# 05_iMX_8X_PCIE.net
KiCad netlist of a schematic drawn in Altium Designer
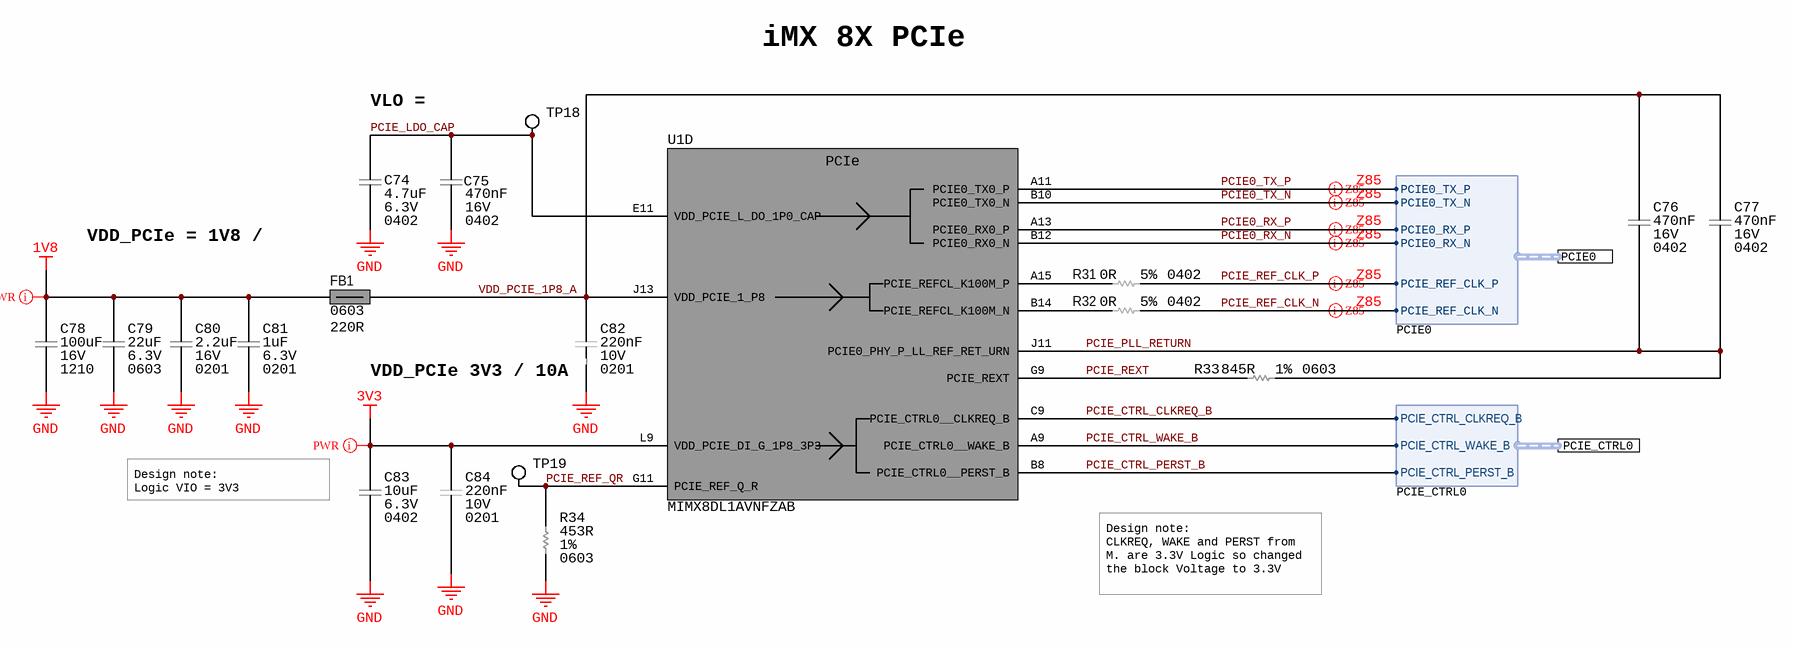
[diagram p0: 05_iMX 8X_PCIE.SchDoc]

(export (version "E")
  (design (tool "Eeschema 10.0.6"))
  (components
    (comp (ref "C74")
      (value "C1005X5R0J475M050BC")
      (footprint "CAP_0402_CAPC1005X05N")
      (description "Multilayer Ceramic Capacitor, 4.7 uF, 6.3 V, ± 20%, X5R, 0402 [1005 Metric]")
      (fields
        (field (name "MANUFACTURER") "TDK")
        (field (name "TOLERANCE") "20%")
        (field (name "CAPACITANCE") "4.7uF")
        (field (name "VOLTAGE RATING") "6.3V")
        (field (name "CASE/PACKAGE") "0402")
      )
      (libsource (lib "Electronic Devices_LIB") (part "CAP_4.7UF_6.3V_X5R_0402"))
    )
    (comp (ref "C75")
      (value "GRT155R61C474KE01D")
      (footprint "CAP_0402_CAPC1005X05N")
      (description "0402 0.47 uF 16 V ±10 % Tolerance X5R SMT Multilayer Ceramic Capacitor")
      (fields
        (field (name "MANUFACTURER") "Murata")
        (field (name "TOLERANCE") "10%")
        (field (name "VOLTAGE RATING") "16V")
        (field (name "CAPACITANCE") "470nF")
        (field (name "CASE/PACKAGE") "0402")
      )
      (libsource (lib "Electronic Devices_LIB") (part "CAP_0.47UF_16V_X5R_0402"))
    )
    (comp (ref "C76")
      (value "GRT155R61C474KE01D")
      (footprint "CAP_0402_CAPC1005X05N")
      (description "0402 0.47 uF 16 V ±10 % Tolerance X5R SMT Multilayer Ceramic Capacitor")
      (fields
        (field (name "MANUFACTURER") "Murata")
        (field (name "TOLERANCE") "10%")
        (field (name "VOLTAGE RATING") "16V")
        (field (name "CAPACITANCE") "470nF")
        (field (name "CASE/PACKAGE") "0402")
      )
      (libsource (lib "Electronic Devices_LIB") (part "CAP_0.47UF_16V_X5R_0402"))
    )
    (comp (ref "C77")
      (value "GRT155R61C474KE01D")
      (footprint "CAP_0402_CAPC1005X05N")
      (description "0402 0.47 uF 16 V ±10 % Tolerance X5R SMT Multilayer Ceramic Capacitor")
      (fields
        (field (name "MANUFACTURER") "Murata")
        (field (name "TOLERANCE") "10%")
        (field (name "VOLTAGE RATING") "16V")
        (field (name "CAPACITANCE") "470nF")
        (field (name "CASE/PACKAGE") "0402")
      )
      (libsource (lib "Electronic Devices_LIB") (part "CAP_0.47UF_16V_X5R_0402"))
    )
    (comp (ref "C78")
      (value "EMK325ABJ107MM-T")
      (footprint "CAP_1210_CAPC3225X270N")
      (description "Multilayer Ceramic Capacitor, 100 uF, 16 V, ± 20%, X5R, 1210 [3225 Metric]")
      (fields
        (field (name "MANUFACTURER") "Taiyo Yuden")
        (field (name "TOLERANCE") "20%")
        (field (name "VOLTAGE RATING") "16V")
        (field (name "CAPACITANCE") "100uF")
        (field (name "CASE/PACKAGE") "1210")
      )
      (libsource (lib "Electronic Devices_LIB") (part "CAP_100UF_16V_X5R_1210"))
    )
    (comp (ref "C79")
      (value "GRM188R60J226MEA0D")
      (footprint "CAP_0603_CAPC1608X08N")
      (description "Multilayer Ceramic Capacitor, 22 uF, 6.3 V, ï¿½ 20%, X5R, 0603 [1608 Metric]")
      (fields
        (field (name "MANUFACTURER") "Murata")
        (field (name "TOLERANCE") "20%")
        (field (name "VOLTAGE RATING") "6.3V")
        (field (name "CAPACITANCE") "22uF")
        (field (name "CASE/PACKAGE") "0603")
      )
      (libsource (lib "Electronic Devices_LIB") (part "CAP_22uF_6.3V_X5R_0603"))
    )
    (comp (ref "C80")
      (value "GRM035R61C225ME01D")
      (footprint "CAP_0201_CAPC0603X03N")
      (description "General Up to 85C Reflow soldering")
      (fields
        (field (name "MANUFACTURER") "Murata")
        (field (name "TOLERANCE") "20%")
        (field (name "CAPACITANCE") "2.2uF")
        (field (name "VOLTAGE RATING") "16V")
        (field (name "CASE/PACKAGE") "0201")
      )
      (libsource (lib "Electronic Devices_LIB") (part "CAP_2.2uF_16V_X5R_0201"))
    )
    (comp (ref "C81")
      (value "02016D105MAT2A")
      (footprint "CAP_0201_CAPC0603X03N")
      (description "0201 1 uF 6.3 V ±20 % Tolerance X5R Surface Mount Multilayer Ceramic Capacitor")
      (fields
        (field (name "MANUFACTURER") "Kyocera AVX")
        (field (name "TOLERANCE") "20%")
        (field (name "VOLTAGE RATING (DC)") "6.3V")
        (field (name "CAPACITANCE") "1uF")
        (field (name "CASE/PACKAGE") "0201")
      )
      (libsource (lib "Electronic Devices_LIB") (part "CAP_1UF_6.3V_X5R_0201"))
    )
    (comp (ref "C82")
      (value "LMK063BJ224MP-F")
      (footprint "CAP_0201_CAPC0603X03N")
      (description "Multilayer Ceramic Capacitors (High dielectric type), 10V, 0.22 uF, ± 20 %, 0201, X5R, RoHS")
      (fields
        (field (name "MANUFACTURER") "Taiyo Yuden")
        (field (name "TOLERANCE") "20%")
        (field (name "VOLTAGE RATING (DC)") "10V")
        (field (name "CAPACITANCE") "220nF")
        (field (name "CASE/PACKAGE") "0201")
      )
      (libsource (lib "Electronic Devices_LIB") (part "CAP_0.22UF_10V_X5R_0201"))
    )
    (comp (ref "C83")
      (value "CL05A106MQ5NUNC")
      (footprint "CAP_0402_CAPC1005X05N")
      (description "Cap Ceramic 10uF 6.3V X5R 20% SMD 0402 85C T/R")
      (fields
        (field (name "MANUFACTURER") "Samsung")
        (field (name "TOLERANCE") "20%")
        (field (name "CASE/PACKAGE") "0402")
        (field (name "CAPACITANCE") "10uF")
        (field (name "VOLTAGE RATING") "6.3V")
      )
      (libsource (lib "Electronic Devices_LIB") (part "CAP_10UF_6.3V_X5R_0402"))
    )
    (comp (ref "C84")
      (value "LMK063BJ224MP-F")
      (footprint "CAP_0201_CAPC0603X03N")
      (description "Multilayer Ceramic Capacitors (High dielectric type), 10V, 0.22 uF, ± 20 %, 0201, X5R, RoHS")
      (fields
        (field (name "MANUFACTURER") "Taiyo Yuden")
        (field (name "TOLERANCE") "20%")
        (field (name "VOLTAGE RATING (DC)") "10V")
        (field (name "CAPACITANCE") "220nF")
        (field (name "CASE/PACKAGE") "0201")
      )
      (libsource (lib "Electronic Devices_LIB") (part "CAP_0.22UF_10V_X5R_0201"))
    )
    (comp (ref "FB1")
      (value "BLM18SG221TN1D")
      (footprint "IND_0603_INDC1608X08N")
      (description "Ferrite Beads Multi-Layer 220Ohm 25% 100MHz 2.5A 40mOhm DCR 0603 Paper T/R")
      (fields
        (field (name "MANUFACTURER") "Murata")
        (field (name "TOLERANCE") "25%")
        (field (name "CASE/PACKAGE") "0603")
        (field (name "IMPEDANCE") "220R")
      )
      (libsource (lib "Electronic Devices_LIB") (part "IND_FERRITE_BEADS_220R_2.5A_BLM18SG221TN1D"))
    )
    (comp (ref "R31")
      (value "ERJ-2GE0R00X")
      (footprint "RES_0402_RESC1005X04N")
      (description "SMD Chip Resistor, Jumper, 0 ohm, 100 mW, 0402 [1005 Metric], Thick Film, General Purpose")
      (fields
        (field (name "MANUFACTURER") "Panasonic")
        (field (name "CASE CODE (IMPERIAL)") "0402")
        (field (name "TOLERANCE") "5%")
        (field (name "RESISTANCE") "0R")
      )
      (libsource (lib "Electronic Devices_LIB") (part "RES_0R_5%_100mW_0402"))
    )
    (comp (ref "R32")
      (value "ERJ-2GE0R00X")
      (footprint "RES_0402_RESC1005X04N")
      (description "SMD Chip Resistor, Jumper, 0 ohm, 100 mW, 0402 [1005 Metric], Thick Film, General Purpose")
      (fields
        (field (name "MANUFACTURER") "Panasonic")
        (field (name "CASE CODE (IMPERIAL)") "0402")
        (field (name "TOLERANCE") "5%")
        (field (name "RESISTANCE") "0R")
      )
      (libsource (lib "Electronic Devices_LIB") (part "RES_0R_5%_100mW_0402"))
    )
    (comp (ref "R33")
      (value "RC0603FR-07845RL")
      (description "SMD Chip Resistor, 845 Ohm, ± 1%, 100 mW, 0603 [1608 Metric], Thick Film, General Purpose")
      (fields
        (field (name "MANUFACTURER") "Yageo")
        (field (name "TOLERANCE") "1%")
        (field (name "RESISTANCE") "845R")
        (field (name "CASE/PACKAGE") "0603")
      )
      (libsource (lib "Electronic Devices_LIB") (part "RES_845R_1%_100mW_0603"))
    )
    (comp (ref "R34")
      (value "CRCW0603453RFKEA")
      (description "Res Thick Film 0603 453 Ohm 1% 0.1W(1/10W) ±100ppm/C Pad SMD T/R Automotive AEC-Q200")
      (fields
        (field (name "MANUFACTURER") "Vishay")
        (field (name "TOLERANCE") "1%")
        (field (name "RESISTANCE") "453R")
        (field (name "RESISTANCE TOLERANCE") "1%")
        (field (name "CASE/PACKAGE") "0603")
      )
      (libsource (lib "Electronic Devices_LIB") (part "RES_453R_1%_100mW_0603"))
    )
    (comp (ref "TP18")
      (value "NO COMPONENT")
      (footprint "TP_PAD_0.5MM_SMD_ROUND")
      (description "Test Point, SMD pad, round, 1.5mm, 1.6mm, 3mm diameter")
      (libsource (lib "Electronic Devices_LIB") (part "TP_PAD_SMD_SMALL"))
    )
    (comp (ref "TP19")
      (value "NO COMPONENT")
      (footprint "TP_PAD_0.5MM_SMD_ROUND")
      (description "Test Point, SMD pad, round, 1.5mm, 1.6mm, 3mm diameter")
      (libsource (lib "Electronic Devices_LIB") (part "TP_PAD_SMD_SMALL"))
    )
    (comp (ref "U1")
      (value "MIMX8DL1AVNFZAB")
      (footprint "MIMX8DL1AVNFZAB")
      (description "I.MX8 Dxl 15SQ / Tray Rohs Compliant: Yes")
      (fields (field (name "MANUFACTURER") "NXP Semiconductors"))
      (libsource (lib "Electronic Devices_LIB") (part "IC_MPU_ARM_1.2GHz_MIMX8DL1AVNFZAB"))
    )
  )
  (nets
    (net (code "3") (name "/PCIE0_RX_N") (class "Default")
      (node (ref "U1") (pin "B12") (pinfunction "PCIE0_RX0_N_B12") (pintype "passive"))
    )
    (net (code "4") (name "/PCIE0_RX_P") (class "Default")
      (node (ref "U1") (pin "A13") (pinfunction "PCIE0_RX0_P_A13") (pintype "passive"))
    )
    (net (code "5") (name "/PCIE0_TX_N") (class "Default")
      (node (ref "U1") (pin "B10") (pinfunction "PCIE0_TX0_N_B10") (pintype "passive"))
    )
    (net (code "6") (name "/PCIE0_TX_P") (class "Default")
      (node (ref "U1") (pin "A11") (pinfunction "PCIE0_TX0_P_A11") (pintype "passive"))
    )
    (net (code "7") (name "/PCIE_CTRL_CLKREQ_B") (class "Default")
      (node (ref "U1") (pin "C9") (pinfunction "PCIE_CTRL0__CLKREQ_B_C9") (pintype "passive"))
    )
    (net (code "8") (name "/PCIE_CTRL_PERST_B") (class "Default")
      (node (ref "U1") (pin "B8") (pinfunction "PCIE_CTRL0__PERST_B_B8") (pintype "passive"))
    )
    (net (code "9") (name "/PCIE_CTRL_WAKE_B") (class "Default")
      (node (ref "U1") (pin "A9") (pinfunction "PCIE_CTRL0__WAKE_B_A9") (pintype "passive"))
    )
    (net (code "10") (name "/PCIE_LDO_CAP") (class "Default")
      (node (ref "C74") (pin "2") (pinfunction "2_2") (pintype "passive"))
      (node (ref "C75") (pin "2") (pinfunction "2_2") (pintype "passive"))
      (node (ref "TP18") (pin "1") (pinfunction "1_1") (pintype "passive"))
      (node (ref "U1") (pin "E11") (pinfunction "VDD_PCIE_L_DO_1P0_CAP_E11") (pintype "passive"))
    )
    (net (code "11") (name "/PCIE_PLL_RETURN") (class "Default")
      (node (ref "C76") (pin "1") (pinfunction "1_1") (pintype "passive"))
      (node (ref "C77") (pin "1") (pinfunction "1_1") (pintype "passive"))
      (node (ref "R33") (pin "2") (pinfunction "2_2") (pintype "passive"))
      (node (ref "U1") (pin "J11") (pinfunction "PCIE0_PHY_P_LL_REF_RET_URN_J11") (pintype "passive"))
    )
    (net (code "12") (name "/PCIE_REF_CLK_N") (class "Default")
      (node (ref "R32") (pin "2") (pinfunction "2_2") (pintype "passive"))
    )
    (net (code "13") (name "/PCIE_REF_CLK_P") (class "Default")
      (node (ref "R31") (pin "2") (pinfunction "2_2") (pintype "passive"))
    )
    (net (code "14") (name "/PCIE_REF_QR") (class "Default")
      (node (ref "R34") (pin "2") (pinfunction "2_2") (pintype "passive"))
      (node (ref "TP19") (pin "1") (pinfunction "1_1") (pintype "passive"))
      (node (ref "U1") (pin "G11") (pinfunction "PCIE_REF_Q_R_G11") (pintype "passive"))
    )
    (net (code "15") (name "/PCIE_REXT") (class "Default")
      (node (ref "R33") (pin "1") (pinfunction "1_1") (pintype "passive"))
      (node (ref "U1") (pin "G9") (pinfunction "PCIE_REXT_G9") (pintype "passive"))
    )
    (net (code "16") (name "/VDD_PCIE_1P8_A") (class "Default")
      (node (ref "C76") (pin "2") (pinfunction "2_2") (pintype "passive"))
      (node (ref "C77") (pin "2") (pinfunction "2_2") (pintype "passive"))
      (node (ref "C82") (pin "2") (pinfunction "2_2") (pintype "passive"))
      (node (ref "FB1") (pin "2") (pinfunction "2_2") (pintype "passive"))
      (node (ref "U1") (pin "J13") (pinfunction "VDD_PCIE_1_P8_J13") (pintype "passive"))
    )
    (net (code "19") (name "1V8") (class "Default")
      (node (ref "C78") (pin "2") (pinfunction "2_2") (pintype "passive"))
      (node (ref "C79") (pin "2") (pinfunction "2_2") (pintype "passive"))
      (node (ref "C80") (pin "2") (pinfunction "2_2") (pintype "passive"))
      (node (ref "C81") (pin "2") (pinfunction "2_2") (pintype "passive"))
      (node (ref "FB1") (pin "1") (pinfunction "1_1") (pintype "passive"))
    )
    (net (code "20") (name "3V3") (class "Default")
      (node (ref "C83") (pin "2") (pinfunction "2_2") (pintype "passive"))
      (node (ref "C84") (pin "2") (pinfunction "2_2") (pintype "passive"))
      (node (ref "U1") (pin "L9") (pinfunction "VDD_PCIE_DI_G_1P8_3P3_L9") (pintype "passive"))
    )
    (net (code "21") (name "GND") (class "Default")
      (node (ref "C74") (pin "1") (pinfunction "1_1") (pintype "passive"))
      (node (ref "C75") (pin "1") (pinfunction "1_1") (pintype "passive"))
      (node (ref "C78") (pin "1") (pinfunction "1_1") (pintype "passive"))
      (node (ref "C79") (pin "1") (pinfunction "1_1") (pintype "passive"))
      (node (ref "C80") (pin "1") (pinfunction "1_1") (pintype "passive"))
      (node (ref "C81") (pin "1") (pinfunction "1_1") (pintype "passive"))
      (node (ref "C82") (pin "1") (pinfunction "1_1") (pintype "passive"))
      (node (ref "C83") (pin "1") (pinfunction "1_1") (pintype "passive"))
      (node (ref "C84") (pin "1") (pinfunction "1_1") (pintype "passive"))
      (node (ref "R34") (pin "1") (pinfunction "1_1") (pintype "passive"))
    )
    (net (code "22") (name "Net-(U1D-PCIE_REFCL_K100M_N)") (class "Default")
      (node (ref "R32") (pin "1") (pinfunction "1_1") (pintype "passive"))
      (node (ref "U1") (pin "B14") (pinfunction "PCIE_REFCL_K100M_N_B14") (pintype "passive"))
    )
    (net (code "23") (name "Net-(U1D-PCIE_REFCL_K100M_P)") (class "Default")
      (node (ref "R31") (pin "1") (pinfunction "1_1") (pintype "passive"))
      (node (ref "U1") (pin "A15") (pinfunction "PCIE_REFCL_K100M_P_A15") (pintype "passive"))
    )
  )
)
